# Schematic_LED_SHIELD_MOTOR_CONTROLLER_V2.net
KiCad netlist of a schematic drawn in Altium Designer
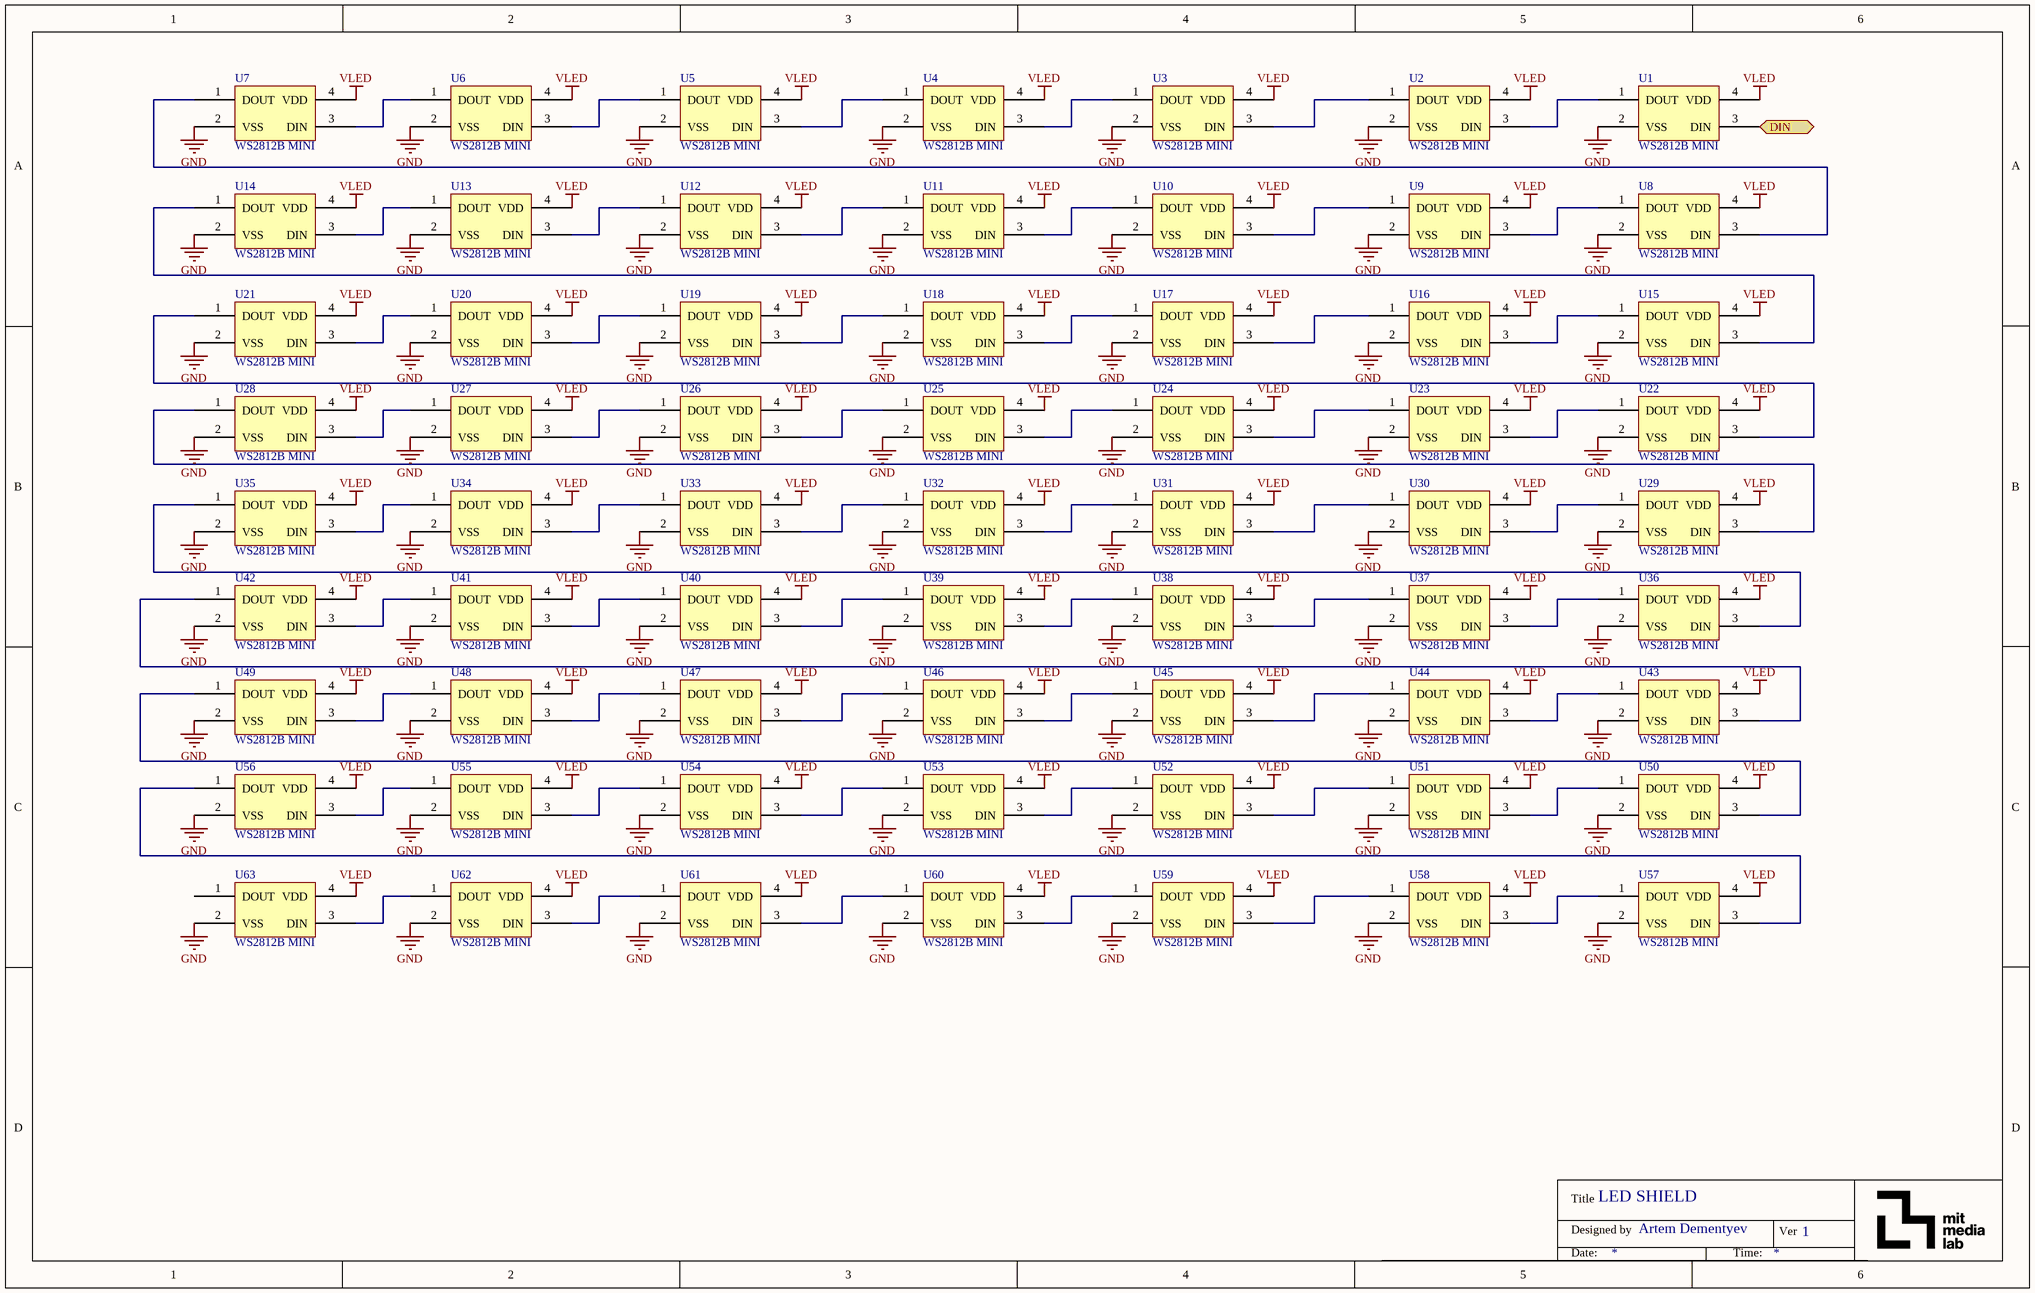
[diagram p0: Schematic_LED_SHIELD_MOTOR_CONTROLLER_V2.SchDoc]

(export (version "E")
  (design (tool "Eeschema 10.0.6"))
  (components
    (comp (ref "U1")
      (value "WS2812B MINI")
      (footprint "WS2812B MINI")
      (libsource (lib "Artem_Library") (part "WS2812B MINI"))
    )
    (comp (ref "U2")
      (value "WS2812B MINI")
      (footprint "WS2812B MINI")
      (libsource (lib "Artem_Library") (part "WS2812B MINI"))
    )
    (comp (ref "U3")
      (value "WS2812B MINI")
      (footprint "WS2812B MINI")
      (libsource (lib "Artem_Library") (part "WS2812B MINI"))
    )
    (comp (ref "U4")
      (value "WS2812B MINI")
      (footprint "WS2812B MINI")
      (libsource (lib "Artem_Library") (part "WS2812B MINI"))
    )
    (comp (ref "U5")
      (value "WS2812B MINI")
      (footprint "WS2812B MINI")
      (libsource (lib "Artem_Library") (part "WS2812B MINI"))
    )
    (comp (ref "U6")
      (value "WS2812B MINI")
      (footprint "WS2812B MINI")
      (libsource (lib "Artem_Library") (part "WS2812B MINI"))
    )
    (comp (ref "U7")
      (value "WS2812B MINI")
      (footprint "WS2812B MINI")
      (libsource (lib "Artem_Library") (part "WS2812B MINI"))
    )
    (comp (ref "U8")
      (value "WS2812B MINI")
      (footprint "WS2812B MINI")
      (libsource (lib "Artem_Library") (part "WS2812B MINI"))
    )
    (comp (ref "U9")
      (value "WS2812B MINI")
      (footprint "WS2812B MINI")
      (libsource (lib "Artem_Library") (part "WS2812B MINI"))
    )
    (comp (ref "U10")
      (value "WS2812B MINI")
      (footprint "WS2812B MINI")
      (libsource (lib "Artem_Library") (part "WS2812B MINI"))
    )
    (comp (ref "U11")
      (value "WS2812B MINI")
      (footprint "WS2812B MINI")
      (libsource (lib "Artem_Library") (part "WS2812B MINI"))
    )
    (comp (ref "U12")
      (value "WS2812B MINI")
      (footprint "WS2812B MINI")
      (libsource (lib "Artem_Library") (part "WS2812B MINI"))
    )
    (comp (ref "U13")
      (value "WS2812B MINI")
      (footprint "WS2812B MINI")
      (libsource (lib "Artem_Library") (part "WS2812B MINI"))
    )
    (comp (ref "U14")
      (value "WS2812B MINI")
      (footprint "WS2812B MINI")
      (libsource (lib "Artem_Library") (part "WS2812B MINI"))
    )
    (comp (ref "U15")
      (value "WS2812B MINI")
      (footprint "WS2812B MINI")
      (libsource (lib "Artem_Library") (part "WS2812B MINI"))
    )
    (comp (ref "U16")
      (value "WS2812B MINI")
      (footprint "WS2812B MINI")
      (libsource (lib "Artem_Library") (part "WS2812B MINI"))
    )
    (comp (ref "U17")
      (value "WS2812B MINI")
      (footprint "WS2812B MINI")
      (libsource (lib "Artem_Library") (part "WS2812B MINI"))
    )
    (comp (ref "U18")
      (value "WS2812B MINI")
      (footprint "WS2812B MINI")
      (libsource (lib "Artem_Library") (part "WS2812B MINI"))
    )
    (comp (ref "U19")
      (value "WS2812B MINI")
      (footprint "WS2812B MINI")
      (libsource (lib "Artem_Library") (part "WS2812B MINI"))
    )
    (comp (ref "U20")
      (value "WS2812B MINI")
      (footprint "WS2812B MINI")
      (libsource (lib "Artem_Library") (part "WS2812B MINI"))
    )
    (comp (ref "U21")
      (value "WS2812B MINI")
      (footprint "WS2812B MINI")
      (libsource (lib "Artem_Library") (part "WS2812B MINI"))
    )
    (comp (ref "U22")
      (value "WS2812B MINI")
      (footprint "WS2812B MINI")
      (libsource (lib "Artem_Library") (part "WS2812B MINI"))
    )
    (comp (ref "U23")
      (value "WS2812B MINI")
      (footprint "WS2812B MINI")
      (libsource (lib "Artem_Library") (part "WS2812B MINI"))
    )
    (comp (ref "U24")
      (value "WS2812B MINI")
      (footprint "WS2812B MINI")
      (libsource (lib "Artem_Library") (part "WS2812B MINI"))
    )
    (comp (ref "U25")
      (value "WS2812B MINI")
      (footprint "WS2812B MINI")
      (libsource (lib "Artem_Library") (part "WS2812B MINI"))
    )
    (comp (ref "U26")
      (value "WS2812B MINI")
      (footprint "WS2812B MINI")
      (libsource (lib "Artem_Library") (part "WS2812B MINI"))
    )
    (comp (ref "U27")
      (value "WS2812B MINI")
      (footprint "WS2812B MINI")
      (libsource (lib "Artem_Library") (part "WS2812B MINI"))
    )
    (comp (ref "U28")
      (value "WS2812B MINI")
      (footprint "WS2812B MINI")
      (libsource (lib "Artem_Library") (part "WS2812B MINI"))
    )
    (comp (ref "U29")
      (value "WS2812B MINI")
      (footprint "WS2812B MINI")
      (libsource (lib "Artem_Library") (part "WS2812B MINI"))
    )
    (comp (ref "U30")
      (value "WS2812B MINI")
      (footprint "WS2812B MINI")
      (libsource (lib "Artem_Library") (part "WS2812B MINI"))
    )
    (comp (ref "U31")
      (value "WS2812B MINI")
      (footprint "WS2812B MINI")
      (libsource (lib "Artem_Library") (part "WS2812B MINI"))
    )
    (comp (ref "U32")
      (value "WS2812B MINI")
      (footprint "WS2812B MINI")
      (libsource (lib "Artem_Library") (part "WS2812B MINI"))
    )
    (comp (ref "U33")
      (value "WS2812B MINI")
      (footprint "WS2812B MINI")
      (libsource (lib "Artem_Library") (part "WS2812B MINI"))
    )
    (comp (ref "U34")
      (value "WS2812B MINI")
      (footprint "WS2812B MINI")
      (libsource (lib "Artem_Library") (part "WS2812B MINI"))
    )
    (comp (ref "U35")
      (value "WS2812B MINI")
      (footprint "WS2812B MINI")
      (libsource (lib "Artem_Library") (part "WS2812B MINI"))
    )
    (comp (ref "U36")
      (value "WS2812B MINI")
      (footprint "WS2812B MINI")
      (libsource (lib "Artem_Library") (part "WS2812B MINI"))
    )
    (comp (ref "U37")
      (value "WS2812B MINI")
      (footprint "WS2812B MINI")
      (libsource (lib "Artem_Library") (part "WS2812B MINI"))
    )
    (comp (ref "U38")
      (value "WS2812B MINI")
      (footprint "WS2812B MINI")
      (libsource (lib "Artem_Library") (part "WS2812B MINI"))
    )
    (comp (ref "U39")
      (value "WS2812B MINI")
      (footprint "WS2812B MINI")
      (libsource (lib "Artem_Library") (part "WS2812B MINI"))
    )
    (comp (ref "U40")
      (value "WS2812B MINI")
      (footprint "WS2812B MINI")
      (libsource (lib "Artem_Library") (part "WS2812B MINI"))
    )
    (comp (ref "U41")
      (value "WS2812B MINI")
      (footprint "WS2812B MINI")
      (libsource (lib "Artem_Library") (part "WS2812B MINI"))
    )
    (comp (ref "U42")
      (value "WS2812B MINI")
      (footprint "WS2812B MINI")
      (libsource (lib "Artem_Library") (part "WS2812B MINI"))
    )
    (comp (ref "U43")
      (value "WS2812B MINI")
      (footprint "WS2812B MINI")
      (libsource (lib "Artem_Library") (part "WS2812B MINI"))
    )
    (comp (ref "U44")
      (value "WS2812B MINI")
      (footprint "WS2812B MINI")
      (libsource (lib "Artem_Library") (part "WS2812B MINI"))
    )
    (comp (ref "U45")
      (value "WS2812B MINI")
      (footprint "WS2812B MINI")
      (libsource (lib "Artem_Library") (part "WS2812B MINI"))
    )
    (comp (ref "U46")
      (value "WS2812B MINI")
      (footprint "WS2812B MINI")
      (libsource (lib "Artem_Library") (part "WS2812B MINI"))
    )
    (comp (ref "U47")
      (value "WS2812B MINI")
      (footprint "WS2812B MINI")
      (libsource (lib "Artem_Library") (part "WS2812B MINI"))
    )
    (comp (ref "U48")
      (value "WS2812B MINI")
      (footprint "WS2812B MINI")
      (libsource (lib "Artem_Library") (part "WS2812B MINI"))
    )
    (comp (ref "U49")
      (value "WS2812B MINI")
      (footprint "WS2812B MINI")
      (libsource (lib "Artem_Library") (part "WS2812B MINI"))
    )
    (comp (ref "U50")
      (value "WS2812B MINI")
      (footprint "WS2812B MINI")
      (libsource (lib "Artem_Library") (part "WS2812B MINI"))
    )
    (comp (ref "U51")
      (value "WS2812B MINI")
      (footprint "WS2812B MINI")
      (libsource (lib "Artem_Library") (part "WS2812B MINI"))
    )
    (comp (ref "U52")
      (value "WS2812B MINI")
      (footprint "WS2812B MINI")
      (libsource (lib "Artem_Library") (part "WS2812B MINI"))
    )
    (comp (ref "U53")
      (value "WS2812B MINI")
      (footprint "WS2812B MINI")
      (libsource (lib "Artem_Library") (part "WS2812B MINI"))
    )
    (comp (ref "U54")
      (value "WS2812B MINI")
      (footprint "WS2812B MINI")
      (libsource (lib "Artem_Library") (part "WS2812B MINI"))
    )
    (comp (ref "U55")
      (value "WS2812B MINI")
      (footprint "WS2812B MINI")
      (libsource (lib "Artem_Library") (part "WS2812B MINI"))
    )
    (comp (ref "U56")
      (value "WS2812B MINI")
      (footprint "WS2812B MINI")
      (libsource (lib "Artem_Library") (part "WS2812B MINI"))
    )
    (comp (ref "U57")
      (value "WS2812B MINI")
      (footprint "WS2812B MINI")
      (libsource (lib "Artem_Library") (part "WS2812B MINI"))
    )
    (comp (ref "U58")
      (value "WS2812B MINI")
      (footprint "WS2812B MINI")
      (libsource (lib "Artem_Library") (part "WS2812B MINI"))
    )
    (comp (ref "U59")
      (value "WS2812B MINI")
      (footprint "WS2812B MINI")
      (libsource (lib "Artem_Library") (part "WS2812B MINI"))
    )
    (comp (ref "U60")
      (value "WS2812B MINI")
      (footprint "WS2812B MINI")
      (libsource (lib "Artem_Library") (part "WS2812B MINI"))
    )
    (comp (ref "U61")
      (value "WS2812B MINI")
      (footprint "WS2812B MINI")
      (libsource (lib "Artem_Library") (part "WS2812B MINI"))
    )
    (comp (ref "U62")
      (value "WS2812B MINI")
      (footprint "WS2812B MINI")
      (libsource (lib "Artem_Library") (part "WS2812B MINI"))
    )
    (comp (ref "U63")
      (value "WS2812B MINI")
      (footprint "WS2812B MINI")
      (libsource (lib "Artem_Library") (part "WS2812B MINI"))
    )
  )
  (nets
    (net (code "1") (name "/DIN") (class "Default")
      (node (ref "U1") (pin "3") (pinfunction "DIN_3") (pintype "passive"))
    )
    (net (code "2") (name "GND") (class "Default")
      (node (ref "U1") (pin "2") (pinfunction "VSS_2") (pintype "passive"))
      (node (ref "U10") (pin "2") (pinfunction "VSS_2") (pintype "passive"))
      (node (ref "U11") (pin "2") (pinfunction "VSS_2") (pintype "passive"))
      (node (ref "U12") (pin "2") (pinfunction "VSS_2") (pintype "passive"))
      (node (ref "U13") (pin "2") (pinfunction "VSS_2") (pintype "passive"))
      (node (ref "U14") (pin "2") (pinfunction "VSS_2") (pintype "passive"))
      (node (ref "U15") (pin "2") (pinfunction "VSS_2") (pintype "passive"))
      (node (ref "U16") (pin "2") (pinfunction "VSS_2") (pintype "passive"))
      (node (ref "U17") (pin "2") (pinfunction "VSS_2") (pintype "passive"))
      (node (ref "U18") (pin "2") (pinfunction "VSS_2") (pintype "passive"))
      (node (ref "U19") (pin "2") (pinfunction "VSS_2") (pintype "passive"))
      (node (ref "U2") (pin "2") (pinfunction "VSS_2") (pintype "passive"))
      (node (ref "U20") (pin "2") (pinfunction "VSS_2") (pintype "passive"))
      (node (ref "U21") (pin "2") (pinfunction "VSS_2") (pintype "passive"))
      (node (ref "U22") (pin "2") (pinfunction "VSS_2") (pintype "passive"))
      (node (ref "U23") (pin "2") (pinfunction "VSS_2") (pintype "passive"))
      (node (ref "U24") (pin "2") (pinfunction "VSS_2") (pintype "passive"))
      (node (ref "U25") (pin "2") (pinfunction "VSS_2") (pintype "passive"))
      (node (ref "U26") (pin "2") (pinfunction "VSS_2") (pintype "passive"))
      (node (ref "U27") (pin "2") (pinfunction "VSS_2") (pintype "passive"))
      (node (ref "U28") (pin "2") (pinfunction "VSS_2") (pintype "passive"))
      (node (ref "U29") (pin "2") (pinfunction "VSS_2") (pintype "passive"))
      (node (ref "U3") (pin "2") (pinfunction "VSS_2") (pintype "passive"))
      (node (ref "U30") (pin "2") (pinfunction "VSS_2") (pintype "passive"))
      (node (ref "U31") (pin "2") (pinfunction "VSS_2") (pintype "passive"))
      (node (ref "U32") (pin "2") (pinfunction "VSS_2") (pintype "passive"))
      (node (ref "U33") (pin "2") (pinfunction "VSS_2") (pintype "passive"))
      (node (ref "U34") (pin "2") (pinfunction "VSS_2") (pintype "passive"))
      (node (ref "U35") (pin "2") (pinfunction "VSS_2") (pintype "passive"))
      (node (ref "U36") (pin "2") (pinfunction "VSS_2") (pintype "passive"))
      (node (ref "U37") (pin "2") (pinfunction "VSS_2") (pintype "passive"))
      (node (ref "U38") (pin "2") (pinfunction "VSS_2") (pintype "passive"))
      (node (ref "U39") (pin "2") (pinfunction "VSS_2") (pintype "passive"))
      (node (ref "U4") (pin "2") (pinfunction "VSS_2") (pintype "passive"))
      (node (ref "U40") (pin "2") (pinfunction "VSS_2") (pintype "passive"))
      (node (ref "U41") (pin "2") (pinfunction "VSS_2") (pintype "passive"))
      (node (ref "U42") (pin "2") (pinfunction "VSS_2") (pintype "passive"))
      (node (ref "U43") (pin "2") (pinfunction "VSS_2") (pintype "passive"))
      (node (ref "U44") (pin "2") (pinfunction "VSS_2") (pintype "passive"))
      (node (ref "U45") (pin "2") (pinfunction "VSS_2") (pintype "passive"))
      (node (ref "U46") (pin "2") (pinfunction "VSS_2") (pintype "passive"))
      (node (ref "U47") (pin "2") (pinfunction "VSS_2") (pintype "passive"))
      (node (ref "U48") (pin "2") (pinfunction "VSS_2") (pintype "passive"))
      (node (ref "U49") (pin "2") (pinfunction "VSS_2") (pintype "passive"))
      (node (ref "U5") (pin "2") (pinfunction "VSS_2") (pintype "passive"))
      (node (ref "U50") (pin "2") (pinfunction "VSS_2") (pintype "passive"))
      (node (ref "U51") (pin "2") (pinfunction "VSS_2") (pintype "passive"))
      (node (ref "U52") (pin "2") (pinfunction "VSS_2") (pintype "passive"))
      (node (ref "U53") (pin "2") (pinfunction "VSS_2") (pintype "passive"))
      (node (ref "U54") (pin "2") (pinfunction "VSS_2") (pintype "passive"))
      (node (ref "U55") (pin "2") (pinfunction "VSS_2") (pintype "passive"))
      (node (ref "U56") (pin "2") (pinfunction "VSS_2") (pintype "passive"))
      (node (ref "U57") (pin "2") (pinfunction "VSS_2") (pintype "passive"))
      (node (ref "U58") (pin "2") (pinfunction "VSS_2") (pintype "passive"))
      (node (ref "U59") (pin "2") (pinfunction "VSS_2") (pintype "passive"))
      (node (ref "U6") (pin "2") (pinfunction "VSS_2") (pintype "passive"))
      (node (ref "U60") (pin "2") (pinfunction "VSS_2") (pintype "passive"))
      (node (ref "U61") (pin "2") (pinfunction "VSS_2") (pintype "passive"))
      (node (ref "U62") (pin "2") (pinfunction "VSS_2") (pintype "passive"))
      (node (ref "U63") (pin "2") (pinfunction "VSS_2") (pintype "passive"))
      (node (ref "U7") (pin "2") (pinfunction "VSS_2") (pintype "passive"))
      (node (ref "U8") (pin "2") (pinfunction "VSS_2") (pintype "passive"))
      (node (ref "U9") (pin "2") (pinfunction "VSS_2") (pintype "passive"))
    )
    (net (code "3") (name "Net-(U1-DOUT)") (class "Default")
      (node (ref "U1") (pin "1") (pinfunction "DOUT_1") (pintype "passive"))
      (node (ref "U2") (pin "3") (pinfunction "DIN_3") (pintype "passive"))
    )
    (net (code "4") (name "Net-(U2-DOUT)") (class "Default")
      (node (ref "U2") (pin "1") (pinfunction "DOUT_1") (pintype "passive"))
      (node (ref "U3") (pin "3") (pinfunction "DIN_3") (pintype "passive"))
    )
    (net (code "5") (name "Net-(U3-DOUT)") (class "Default")
      (node (ref "U3") (pin "1") (pinfunction "DOUT_1") (pintype "passive"))
      (node (ref "U4") (pin "3") (pinfunction "DIN_3") (pintype "passive"))
    )
    (net (code "6") (name "Net-(U4-DOUT)") (class "Default")
      (node (ref "U4") (pin "1") (pinfunction "DOUT_1") (pintype "passive"))
      (node (ref "U5") (pin "3") (pinfunction "DIN_3") (pintype "passive"))
    )
    (net (code "7") (name "Net-(U5-DOUT)") (class "Default")
      (node (ref "U5") (pin "1") (pinfunction "DOUT_1") (pintype "passive"))
      (node (ref "U6") (pin "3") (pinfunction "DIN_3") (pintype "passive"))
    )
    (net (code "8") (name "Net-(U6-DOUT)") (class "Default")
      (node (ref "U6") (pin "1") (pinfunction "DOUT_1") (pintype "passive"))
      (node (ref "U7") (pin "3") (pinfunction "DIN_3") (pintype "passive"))
    )
    (net (code "9") (name "Net-(U7-DOUT)") (class "Default")
      (node (ref "U7") (pin "1") (pinfunction "DOUT_1") (pintype "passive"))
      (node (ref "U8") (pin "3") (pinfunction "DIN_3") (pintype "passive"))
    )
    (net (code "10") (name "Net-(U8-DOUT)") (class "Default")
      (node (ref "U8") (pin "1") (pinfunction "DOUT_1") (pintype "passive"))
      (node (ref "U9") (pin "3") (pinfunction "DIN_3") (pintype "passive"))
    )
    (net (code "11") (name "Net-(U10-DIN)") (class "Default")
      (node (ref "U10") (pin "3") (pinfunction "DIN_3") (pintype "passive"))
      (node (ref "U9") (pin "1") (pinfunction "DOUT_1") (pintype "passive"))
    )
    (net (code "12") (name "Net-(U10-DOUT)") (class "Default")
      (node (ref "U10") (pin "1") (pinfunction "DOUT_1") (pintype "passive"))
      (node (ref "U11") (pin "3") (pinfunction "DIN_3") (pintype "passive"))
    )
    (net (code "13") (name "Net-(U11-DOUT)") (class "Default")
      (node (ref "U11") (pin "1") (pinfunction "DOUT_1") (pintype "passive"))
      (node (ref "U12") (pin "3") (pinfunction "DIN_3") (pintype "passive"))
    )
    (net (code "14") (name "Net-(U12-DOUT)") (class "Default")
      (node (ref "U12") (pin "1") (pinfunction "DOUT_1") (pintype "passive"))
      (node (ref "U13") (pin "3") (pinfunction "DIN_3") (pintype "passive"))
    )
    (net (code "15") (name "Net-(U13-DOUT)") (class "Default")
      (node (ref "U13") (pin "1") (pinfunction "DOUT_1") (pintype "passive"))
      (node (ref "U14") (pin "3") (pinfunction "DIN_3") (pintype "passive"))
    )
    (net (code "16") (name "Net-(U14-DOUT)") (class "Default")
      (node (ref "U14") (pin "1") (pinfunction "DOUT_1") (pintype "passive"))
      (node (ref "U15") (pin "3") (pinfunction "DIN_3") (pintype "passive"))
    )
    (net (code "17") (name "Net-(U15-DOUT)") (class "Default")
      (node (ref "U15") (pin "1") (pinfunction "DOUT_1") (pintype "passive"))
      (node (ref "U16") (pin "3") (pinfunction "DIN_3") (pintype "passive"))
    )
    (net (code "18") (name "Net-(U16-DOUT)") (class "Default")
      (node (ref "U16") (pin "1") (pinfunction "DOUT_1") (pintype "passive"))
      (node (ref "U17") (pin "3") (pinfunction "DIN_3") (pintype "passive"))
    )
    (net (code "19") (name "Net-(U17-DOUT)") (class "Default")
      (node (ref "U17") (pin "1") (pinfunction "DOUT_1") (pintype "passive"))
      (node (ref "U18") (pin "3") (pinfunction "DIN_3") (pintype "passive"))
    )
    (net (code "20") (name "Net-(U18-DOUT)") (class "Default")
      (node (ref "U18") (pin "1") (pinfunction "DOUT_1") (pintype "passive"))
      (node (ref "U19") (pin "3") (pinfunction "DIN_3") (pintype "passive"))
    )
    (net (code "21") (name "Net-(U19-DOUT)") (class "Default")
      (node (ref "U19") (pin "1") (pinfunction "DOUT_1") (pintype "passive"))
      (node (ref "U20") (pin "3") (pinfunction "DIN_3") (pintype "passive"))
    )
    (net (code "22") (name "Net-(U20-DOUT)") (class "Default")
      (node (ref "U20") (pin "1") (pinfunction "DOUT_1") (pintype "passive"))
      (node (ref "U21") (pin "3") (pinfunction "DIN_3") (pintype "passive"))
    )
    (net (code "23") (name "Net-(U21-DOUT)") (class "Default")
      (node (ref "U21") (pin "1") (pinfunction "DOUT_1") (pintype "passive"))
      (node (ref "U22") (pin "3") (pinfunction "DIN_3") (pintype "passive"))
    )
    (net (code "24") (name "Net-(U22-DOUT)") (class "Default")
      (node (ref "U22") (pin "1") (pinfunction "DOUT_1") (pintype "passive"))
      (node (ref "U23") (pin "3") (pinfunction "DIN_3") (pintype "passive"))
    )
    (net (code "25") (name "Net-(U23-DOUT)") (class "Default")
      (node (ref "U23") (pin "1") (pinfunction "DOUT_1") (pintype "passive"))
      (node (ref "U24") (pin "3") (pinfunction "DIN_3") (pintype "passive"))
    )
    (net (code "26") (name "Net-(U24-DOUT)") (class "Default")
      (node (ref "U24") (pin "1") (pinfunction "DOUT_1") (pintype "passive"))
      (node (ref "U25") (pin "3") (pinfunction "DIN_3") (pintype "passive"))
    )
    (net (code "27") (name "Net-(U25-DOUT)") (class "Default")
      (node (ref "U25") (pin "1") (pinfunction "DOUT_1") (pintype "passive"))
      (node (ref "U26") (pin "3") (pinfunction "DIN_3") (pintype "passive"))
    )
    (net (code "28") (name "Net-(U26-DOUT)") (class "Default")
      (node (ref "U26") (pin "1") (pinfunction "DOUT_1") (pintype "passive"))
      (node (ref "U27") (pin "3") (pinfunction "DIN_3") (pintype "passive"))
    )
    (net (code "29") (name "Net-(U27-DOUT)") (class "Default")
      (node (ref "U27") (pin "1") (pinfunction "DOUT_1") (pintype "passive"))
      (node (ref "U28") (pin "3") (pinfunction "DIN_3") (pintype "passive"))
    )
    (net (code "30") (name "Net-(U28-DOUT)") (class "Default")
      (node (ref "U28") (pin "1") (pinfunction "DOUT_1") (pintype "passive"))
      (node (ref "U29") (pin "3") (pinfunction "DIN_3") (pintype "passive"))
    )
    (net (code "31") (name "Net-(U29-DOUT)") (class "Default")
      (node (ref "U29") (pin "1") (pinfunction "DOUT_1") (pintype "passive"))
      (node (ref "U30") (pin "3") (pinfunction "DIN_3") (pintype "passive"))
    )
    (net (code "32") (name "Net-(U30-DOUT)") (class "Default")
      (node (ref "U30") (pin "1") (pinfunction "DOUT_1") (pintype "passive"))
      (node (ref "U31") (pin "3") (pinfunction "DIN_3") (pintype "passive"))
    )
    (net (code "33") (name "Net-(U31-DOUT)") (class "Default")
      (node (ref "U31") (pin "1") (pinfunction "DOUT_1") (pintype "passive"))
      (node (ref "U32") (pin "3") (pinfunction "DIN_3") (pintype "passive"))
    )
    (net (code "34") (name "Net-(U32-DOUT)") (class "Default")
      (node (ref "U32") (pin "1") (pinfunction "DOUT_1") (pintype "passive"))
      (node (ref "U33") (pin "3") (pinfunction "DIN_3") (pintype "passive"))
    )
    (net (code "35") (name "Net-(U33-DOUT)") (class "Default")
      (node (ref "U33") (pin "1") (pinfunction "DOUT_1") (pintype "passive"))
      (node (ref "U34") (pin "3") (pinfunction "DIN_3") (pintype "passive"))
    )
    (net (code "36") (name "Net-(U34-DOUT)") (class "Default")
      (node (ref "U34") (pin "1") (pinfunction "DOUT_1") (pintype "passive"))
      (node (ref "U35") (pin "3") (pinfunction "DIN_3") (pintype "passive"))
    )
    (net (code "37") (name "Net-(U35-DOUT)") (class "Default")
      (node (ref "U35") (pin "1") (pinfunction "DOUT_1") (pintype "passive"))
      (node (ref "U36") (pin "3") (pinfunction "DIN_3") (pintype "passive"))
    )
    (net (code "38") (name "Net-(U36-DOUT)") (class "Default")
      (node (ref "U36") (pin "1") (pinfunction "DOUT_1") (pintype "passive"))
      (node (ref "U37") (pin "3") (pinfunction "DIN_3") (pintype "passive"))
    )
    (net (code "39") (name "Net-(U37-DOUT)") (class "Default")
      (node (ref "U37") (pin "1") (pinfunction "DOUT_1") (pintype "passive"))
      (node (ref "U38") (pin "3") (pinfunction "DIN_3") (pintype "passive"))
    )
    (net (code "40") (name "Net-(U38-DOUT)") (class "Default")
      (node (ref "U38") (pin "1") (pinfunction "DOUT_1") (pintype "passive"))
      (node (ref "U39") (pin "3") (pinfunction "DIN_3") (pintype "passive"))
    )
    (net (code "41") (name "Net-(U39-DOUT)") (class "Default")
      (node (ref "U39") (pin "1") (pinfunction "DOUT_1") (pintype "passive"))
      (node (ref "U40") (pin "3") (pinfunction "DIN_3") (pintype "passive"))
    )
    (net (code "42") (name "Net-(U40-DOUT)") (class "Default")
      (node (ref "U40") (pin "1") (pinfunction "DOUT_1") (pintype "passive"))
      (node (ref "U41") (pin "3") (pinfunction "DIN_3") (pintype "passive"))
    )
    (net (code "43") (name "Net-(U41-DOUT)") (class "Default")
      (node (ref "U41") (pin "1") (pinfunction "DOUT_1") (pintype "passive"))
      (node (ref "U42") (pin "3") (pinfunction "DIN_3") (pintype "passive"))
    )
    (net (code "44") (name "Net-(U42-DOUT)") (class "Default")
      (node (ref "U42") (pin "1") (pinfunction "DOUT_1") (pintype "passive"))
      (node (ref "U43") (pin "3") (pinfunction "DIN_3") (pintype "passive"))
    )
    (net (code "45") (name "Net-(U43-DOUT)") (class "Default")
      (node (ref "U43") (pin "1") (pinfunction "DOUT_1") (pintype "passive"))
      (node (ref "U44") (pin "3") (pinfunction "DIN_3") (pintype "passive"))
    )
    (net (code "46") (name "Net-(U44-DOUT)") (class "Default")
      (node (ref "U44") (pin "1") (pinfunction "DOUT_1") (pintype "passive"))
      (node (ref "U45") (pin "3") (pinfunction "DIN_3") (pintype "passive"))
    )
    (net (code "47") (name "Net-(U45-DOUT)") (class "Default")
      (node (ref "U45") (pin "1") (pinfunction "DOUT_1") (pintype "passive"))
      (node (ref "U46") (pin "3") (pinfunction "DIN_3") (pintype "passive"))
    )
    (net (code "48") (name "Net-(U46-DOUT)") (class "Default")
      (node (ref "U46") (pin "1") (pinfunction "DOUT_1") (pintype "passive"))
      (node (ref "U47") (pin "3") (pinfunction "DIN_3") (pintype "passive"))
    )
    (net (code "49") (name "Net-(U47-DOUT)") (class "Default")
      (node (ref "U47") (pin "1") (pinfunction "DOUT_1") (pintype "passive"))
      (node (ref "U48") (pin "3") (pinfunction "DIN_3") (pintype "passive"))
    )
    (net (code "50") (name "Net-(U48-DOUT)") (class "Default")
      (node (ref "U48") (pin "1") (pinfunction "DOUT_1") (pintype "passive"))
      (node (ref "U49") (pin "3") (pinfunction "DIN_3") (pintype "passive"))
    )
    (net (code "51") (name "Net-(U49-DOUT)") (class "Default")
      (node (ref "U49") (pin "1") (pinfunction "DOUT_1") (pintype "passive"))
      (node (ref "U50") (pin "3") (pinfunction "DIN_3") (pintype "passive"))
    )
    (net (code "52") (name "Net-(U50-DOUT)") (class "Default")
      (node (ref "U50") (pin "1") (pinfunction "DOUT_1") (pintype "passive"))
      (node (ref "U51") (pin "3") (pinfunction "DIN_3") (pintype "passive"))
    )
    (net (code "53") (name "Net-(U51-DOUT)") (class "Default")
      (node (ref "U51") (pin "1") (pinfunction "DOUT_1") (pintype "passive"))
      (node (ref "U52") (pin "3") (pinfunction "DIN_3") (pintype "passive"))
    )
    (net (code "54") (name "Net-(U52-DOUT)") (class "Default")
      (node (ref "U52") (pin "1") (pinfunction "DOUT_1") (pintype "passive"))
      (node (ref "U53") (pin "3") (pinfunction "DIN_3") (pintype "passive"))
    )
    (net (code "55") (name "Net-(U53-DOUT)") (class "Default")
      (node (ref "U53") (pin "1") (pinfunction "DOUT_1") (pintype "passive"))
      (node (ref "U54") (pin "3") (pinfunction "DIN_3") (pintype "passive"))
    )
    (net (code "56") (name "Net-(U54-DOUT)") (class "Default")
      (node (ref "U54") (pin "1") (pinfunction "DOUT_1") (pintype "passive"))
      (node (ref "U55") (pin "3") (pinfunction "DIN_3") (pintype "passive"))
    )
    (net (code "57") (name "Net-(U55-DOUT)") (class "Default")
      (node (ref "U55") (pin "1") (pinfunction "DOUT_1") (pintype "passive"))
      (node (ref "U56") (pin "3") (pinfunction "DIN_3") (pintype "passive"))
    )
    (net (code "58") (name "Net-(U56-DOUT)") (class "Default")
      (node (ref "U56") (pin "1") (pinfunction "DOUT_1") (pintype "passive"))
      (node (ref "U57") (pin "3") (pinfunction "DIN_3") (pintype "passive"))
    )
    (net (code "59") (name "Net-(U57-DOUT)") (class "Default")
      (node (ref "U57") (pin "1") (pinfunction "DOUT_1") (pintype "passive"))
      (node (ref "U58") (pin "3") (pinfunction "DIN_3") (pintype "passive"))
    )
    (net (code "60") (name "Net-(U58-DOUT)") (class "Default")
      (node (ref "U58") (pin "1") (pinfunction "DOUT_1") (pintype "passive"))
      (node (ref "U59") (pin "3") (pinfunction "DIN_3") (pintype "passive"))
    )
    (net (code "61") (name "Net-(U59-DOUT)") (class "Default")
      (node (ref "U59") (pin "1") (pinfunction "DOUT_1") (pintype "passive"))
      (node (ref "U60") (pin "3") (pinfunction "DIN_3") (pintype "passive"))
    )
    (net (code "62") (name "Net-(U60-DOUT)") (class "Default")
      (node (ref "U60") (pin "1") (pinfunction "DOUT_1") (pintype "passive"))
      (node (ref "U61") (pin "3") (pinfunction "DIN_3") (pintype "passive"))
    )
    (net (code "63") (name "Net-(U61-DOUT)") (class "Default")
      (node (ref "U61") (pin "1") (pinfunction "DOUT_1") (pintype "passive"))
      (node (ref "U62") (pin "3") (pinfunction "DIN_3") (pintype "passive"))
    )
    (net (code "64") (name "Net-(U62-DOUT)") (class "Default")
      (node (ref "U62") (pin "1") (pinfunction "DOUT_1") (pintype "passive"))
      (node (ref "U63") (pin "3") (pinfunction "DIN_3") (pintype "passive"))
    )
    (net (code "65") (name "VLED") (class "Default")
      (node (ref "U1") (pin "4") (pinfunction "VDD_4") (pintype "passive"))
      (node (ref "U10") (pin "4") (pinfunction "VDD_4") (pintype "passive"))
      (node (ref "U11") (pin "4") (pinfunction "VDD_4") (pintype "passive"))
      (node (ref "U12") (pin "4") (pinfunction "VDD_4") (pintype "passive"))
      (node (ref "U13") (pin "4") (pinfunction "VDD_4") (pintype "passive"))
      (node (ref "U14") (pin "4") (pinfunction "VDD_4") (pintype "passive"))
      (node (ref "U15") (pin "4") (pinfunction "VDD_4") (pintype "passive"))
      (node (ref "U16") (pin "4") (pinfunction "VDD_4") (pintype "passive"))
      (node (ref "U17") (pin "4") (pinfunction "VDD_4") (pintype "passive"))
      (node (ref "U18") (pin "4") (pinfunction "VDD_4") (pintype "passive"))
      (node (ref "U19") (pin "4") (pinfunction "VDD_4") (pintype "passive"))
      (node (ref "U2") (pin "4") (pinfunction "VDD_4") (pintype "passive"))
      (node (ref "U20") (pin "4") (pinfunction "VDD_4") (pintype "passive"))
      (node (ref "U21") (pin "4") (pinfunction "VDD_4") (pintype "passive"))
      (node (ref "U22") (pin "4") (pinfunction "VDD_4") (pintype "passive"))
      (node (ref "U23") (pin "4") (pinfunction "VDD_4") (pintype "passive"))
      (node (ref "U24") (pin "4") (pinfunction "VDD_4") (pintype "passive"))
      (node (ref "U25") (pin "4") (pinfunction "VDD_4") (pintype "passive"))
      (node (ref "U26") (pin "4") (pinfunction "VDD_4") (pintype "passive"))
      (node (ref "U27") (pin "4") (pinfunction "VDD_4") (pintype "passive"))
      (node (ref "U28") (pin "4") (pinfunction "VDD_4") (pintype "passive"))
      (node (ref "U29") (pin "4") (pinfunction "VDD_4") (pintype "passive"))
      (node (ref "U3") (pin "4") (pinfunction "VDD_4") (pintype "passive"))
      (node (ref "U30") (pin "4") (pinfunction "VDD_4") (pintype "passive"))
      (node (ref "U31") (pin "4") (pinfunction "VDD_4") (pintype "passive"))
      (node (ref "U32") (pin "4") (pinfunction "VDD_4") (pintype "passive"))
      (node (ref "U33") (pin "4") (pinfunction "VDD_4") (pintype "passive"))
      (node (ref "U34") (pin "4") (pinfunction "VDD_4") (pintype "passive"))
      (node (ref "U35") (pin "4") (pinfunction "VDD_4") (pintype "passive"))
      (node (ref "U36") (pin "4") (pinfunction "VDD_4") (pintype "passive"))
      (node (ref "U37") (pin "4") (pinfunction "VDD_4") (pintype "passive"))
      (node (ref "U38") (pin "4") (pinfunction "VDD_4") (pintype "passive"))
      (node (ref "U39") (pin "4") (pinfunction "VDD_4") (pintype "passive"))
      (node (ref "U4") (pin "4") (pinfunction "VDD_4") (pintype "passive"))
      (node (ref "U40") (pin "4") (pinfunction "VDD_4") (pintype "passive"))
      (node (ref "U41") (pin "4") (pinfunction "VDD_4") (pintype "passive"))
      (node (ref "U42") (pin "4") (pinfunction "VDD_4") (pintype "passive"))
      (node (ref "U43") (pin "4") (pinfunction "VDD_4") (pintype "passive"))
      (node (ref "U44") (pin "4") (pinfunction "VDD_4") (pintype "passive"))
      (node (ref "U45") (pin "4") (pinfunction "VDD_4") (pintype "passive"))
      (node (ref "U46") (pin "4") (pinfunction "VDD_4") (pintype "passive"))
      (node (ref "U47") (pin "4") (pinfunction "VDD_4") (pintype "passive"))
      (node (ref "U48") (pin "4") (pinfunction "VDD_4") (pintype "passive"))
      (node (ref "U49") (pin "4") (pinfunction "VDD_4") (pintype "passive"))
      (node (ref "U5") (pin "4") (pinfunction "VDD_4") (pintype "passive"))
      (node (ref "U50") (pin "4") (pinfunction "VDD_4") (pintype "passive"))
      (node (ref "U51") (pin "4") (pinfunction "VDD_4") (pintype "passive"))
      (node (ref "U52") (pin "4") (pinfunction "VDD_4") (pintype "passive"))
      (node (ref "U53") (pin "4") (pinfunction "VDD_4") (pintype "passive"))
      (node (ref "U54") (pin "4") (pinfunction "VDD_4") (pintype "passive"))
      (node (ref "U55") (pin "4") (pinfunction "VDD_4") (pintype "passive"))
      (node (ref "U56") (pin "4") (pinfunction "VDD_4") (pintype "passive"))
      (node (ref "U57") (pin "4") (pinfunction "VDD_4") (pintype "passive"))
      (node (ref "U58") (pin "4") (pinfunction "VDD_4") (pintype "passive"))
      (node (ref "U59") (pin "4") (pinfunction "VDD_4") (pintype "passive"))
      (node (ref "U6") (pin "4") (pinfunction "VDD_4") (pintype "passive"))
      (node (ref "U60") (pin "4") (pinfunction "VDD_4") (pintype "passive"))
      (node (ref "U61") (pin "4") (pinfunction "VDD_4") (pintype "passive"))
      (node (ref "U62") (pin "4") (pinfunction "VDD_4") (pintype "passive"))
      (node (ref "U63") (pin "4") (pinfunction "VDD_4") (pintype "passive"))
      (node (ref "U7") (pin "4") (pinfunction "VDD_4") (pintype "passive"))
      (node (ref "U8") (pin "4") (pinfunction "VDD_4") (pintype "passive"))
      (node (ref "U9") (pin "4") (pinfunction "VDD_4") (pintype "passive"))
    )
    (net (code "66") (name "unconnected-(U63-DOUT-Pad1)") (class "Default")
      (node (ref "U63") (pin "1") (pinfunction "DOUT_1") (pintype "passive"))
    )
  )
)
